# breakout.net
KiCad netlist of a schematic drawn in Altium Designer
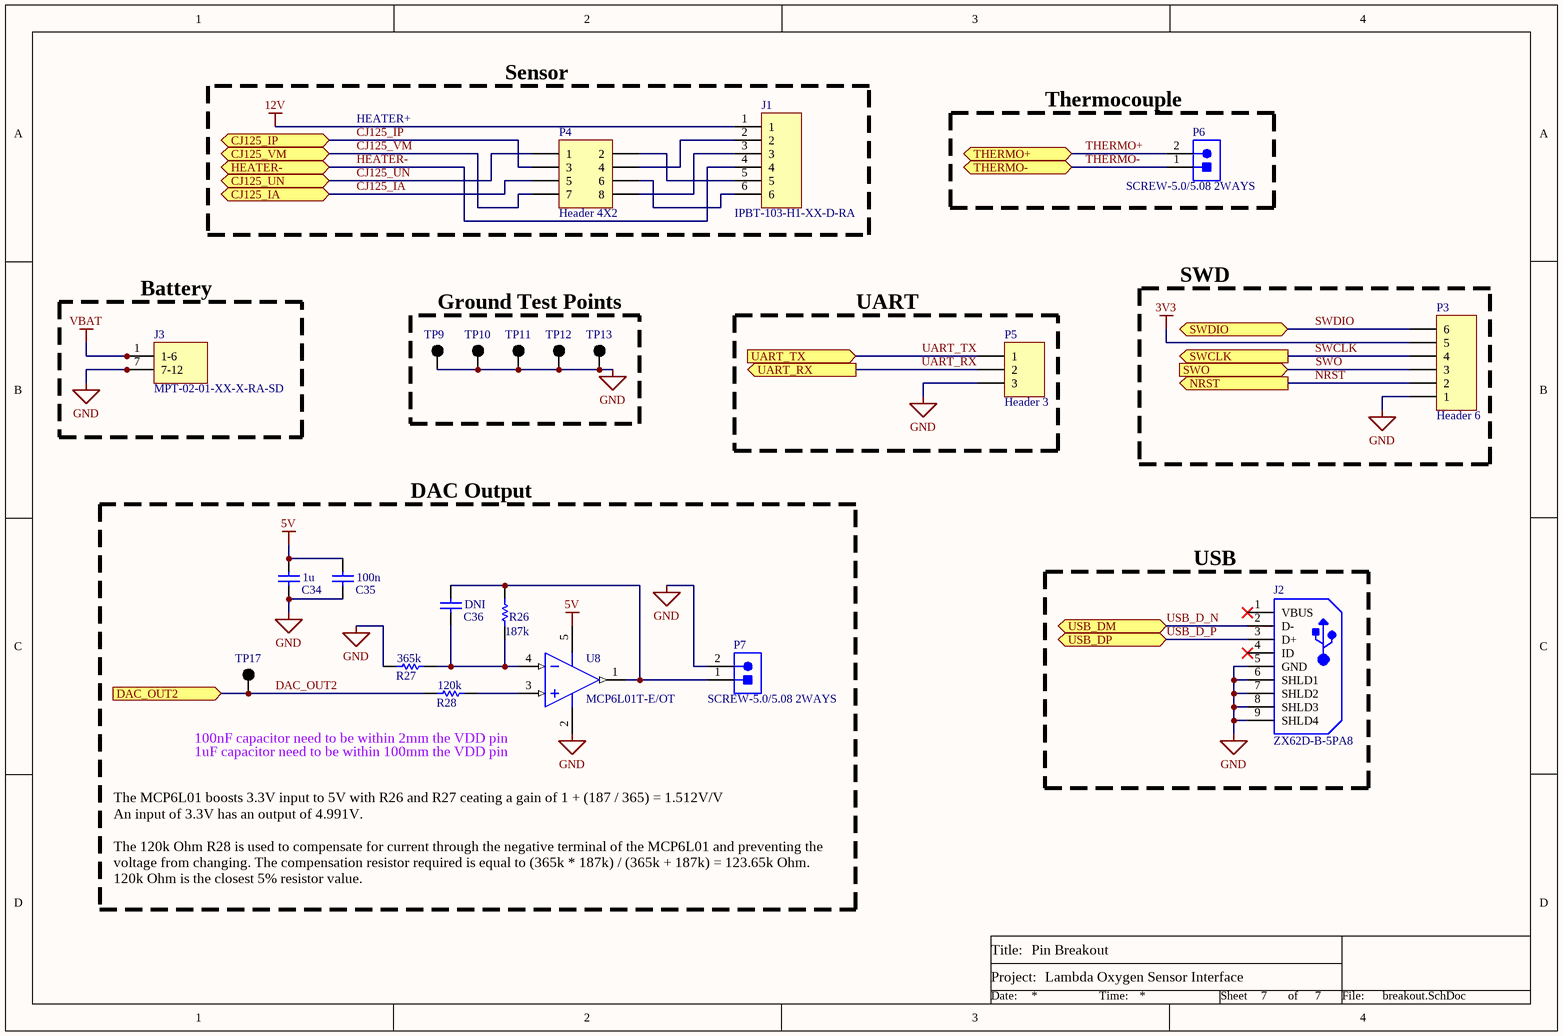
[diagram p0: breakout.SchDoc]

(export (version "E")
  (design (tool "Eeschema 10.0.6"))
  (components
    (comp (ref "C34")
      (value "1u")
      (footprint "1206")
      (description "Generic 1206 Capacitor")
      (libsource (lib "symbol_library") (part "C_1206"))
    )
    (comp (ref "C35")
      (value "100n")
      (footprint "0805")
      (description "Generic 0805 Capacitor")
      (libsource (lib "symbol_library") (part "C_0805"))
    )
    (comp (ref "C36")
      (value "DNI")
      (footprint "0805")
      (description "Generic 0805 Capacitor")
      (libsource (lib "symbol_library") (part "C_0805"))
    )
    (comp (ref "J1")
      (value "IPBT-103-H1-XX-D-RA")
      (footprint "IPBT-103-H1-XX-D-RA")
      (description "0.165 INCH DOUBLE ROW TERMINAL ASSEMBLY")
      (libsource (lib "symbol_library") (part "IPBT-103-H1-XX-D-RA"))
    )
    (comp (ref "J2")
      (value "ZX62D-B-5PA8")
      (footprint "HIRO-ZX62D-B-5PA8_V")
      (description "Micro-USB Connector Meeting USB 2.0 Standard, -30 to 85 degC, 5-Pin SMD, RoHS, Tape and Reel")
      (fields (field (name "MANUFACTURER") "HiroseElectric"))
      (libsource (lib "symbol_library") (part "Micro_USB"))
    )
    (comp (ref "J3")
      (value "MPT-02-01-XX-X-RA-SD")
      (footprint "MPT-02-01-XX-X-RA-SD")
      (libsource (lib "symbol_library") (part "MPT-02-01-XX-X-RA-SD"))
    )
    (comp (ref "P3")
      (value "Header 6")
      (footprint "HDR1X6")
      (description "Header, 6-Pin")
      (fields (field (name "PUBLISHER") "Altium Limited"))
      (libsource (lib "Miscellaneous Connectors") (part "Header 6"))
    )
    (comp (ref "P4")
      (value "Header 4X2")
      (footprint "HDR2X4")
      (description "Header, 4-Pin, Dual row")
      (fields (field (name "PUBLISHER") "Altium Limited"))
      (libsource (lib "Miscellaneous Connectors") (part "Header 4X2"))
    )
    (comp (ref "P5")
      (value "Header 3")
      (footprint "HDR1X3")
      (description "Header, 3-Pin")
      (fields (field (name "PUBLISHER") "Altium Limited"))
      (libsource (lib "Miscellaneous Connectors") (part "Header 3"))
    )
    (comp (ref "P6")
      (value "SCREW-5.0/5.08 2WAYS")
      (footprint "Degson_DG126-5.0-02P-14")
      (description "Socket, Screw Terminal Block, 2 Way, 5.0 mm Pitch, 90 Degree Angle, Through-Hole")
      (fields (field (name "MANUFACTURER") "No Vendor"))
      (libsource (lib "symbol_library") (part "Screw_Header_2"))
    )
    (comp (ref "P7")
      (value "SCREW-5.0/5.08 2WAYS")
      (footprint "Degson_DG126-5.0-02P-14")
      (description "Socket, Screw Terminal Block, 2 Way, 5.0 mm Pitch, 90 Degree Angle, Through-Hole")
      (fields (field (name "MANUFACTURER") "No Vendor"))
      (libsource (lib "symbol_library") (part "Screw_Header_2"))
    )
    (comp (ref "R26")
      (value "187k")
      (footprint "0603")
      (description "Generic 0603 Resistor")
      (libsource (lib "symbol_library") (part "R_0603"))
    )
    (comp (ref "R27")
      (value "365k")
      (footprint "0603")
      (description "Generic 0603 Resistor")
      (libsource (lib "symbol_library") (part "R_0603"))
    )
    (comp (ref "R28")
      (value "120k")
      (footprint "0603")
      (description "Generic 0603 Resistor")
      (libsource (lib "symbol_library") (part "R_0603"))
    )
    (comp (ref "TP9")
      (value "5001")
      (footprint "KSTN-5001")
      (description "Test Point, Black, 1-Pin THD, RoHS, Bulk")
      (fields (field (name "MANUFACTURER") "Keystone"))
      (libsource (lib "symbol_library") (part "TP5001"))
    )
    (comp (ref "TP10")
      (value "5001")
      (footprint "KSTN-5001")
      (description "Test Point, Black, 1-Pin THD, RoHS, Bulk")
      (fields (field (name "MANUFACTURER") "Keystone"))
      (libsource (lib "symbol_library") (part "TP5001"))
    )
    (comp (ref "TP11")
      (value "5001")
      (footprint "KSTN-5001")
      (description "Test Point, Black, 1-Pin THD, RoHS, Bulk")
      (fields (field (name "MANUFACTURER") "Keystone"))
      (libsource (lib "symbol_library") (part "TP5001"))
    )
    (comp (ref "TP12")
      (value "5001")
      (footprint "KSTN-5001")
      (description "Test Point, Black, 1-Pin THD, RoHS, Bulk")
      (fields (field (name "MANUFACTURER") "Keystone"))
      (libsource (lib "symbol_library") (part "TP5001"))
    )
    (comp (ref "TP13")
      (value "5001")
      (footprint "KSTN-5001")
      (description "Test Point, Black, 1-Pin THD, RoHS, Bulk")
      (fields (field (name "MANUFACTURER") "Keystone"))
      (libsource (lib "symbol_library") (part "TP5001"))
    )
    (comp (ref "TP17")
      (value "5001")
      (footprint "KSTN-5001")
      (description "Test Point, Black, 1-Pin THD, RoHS, Bulk")
      (fields (field (name "MANUFACTURER") "Keystone"))
      (libsource (lib "symbol_library") (part "TP5001"))
    )
    (comp (ref "U8")
      (value "MCP6L01T-E/OT")
      (footprint "DDC0005A_M")
      (description "1 MHz, 85 uA Op Amp, 5-Pin SOT-23, Extended Temperature Range")
      (libsource (lib "symbol_library") (part "MCP6L01"))
    )
  )
  (nets
    (net (code "1") (name "/CJ125_IA") (class "Default")
      (node (ref "P4") (pin "5") (pinfunction "5_5") (pintype "passive"))
    )
    (net (code "2") (name "/CJ125_IP") (class "Default")
      (node (ref "P4") (pin "3") (pinfunction "3_3") (pintype "passive"))
    )
    (net (code "3") (name "/CJ125_UN") (class "Default")
      (node (ref "P4") (pin "1") (pinfunction "1_1") (pintype "passive"))
    )
    (net (code "4") (name "/CJ125_VM") (class "Default")
      (node (ref "P4") (pin "7") (pinfunction "7_7") (pintype "passive"))
    )
    (net (code "5") (name "/DAC_OUT2") (class "Default")
      (node (ref "R28") (pin "1") (pinfunction "1_1") (pintype "passive"))
      (node (ref "TP17") (pin "1") (pintype "passive"))
    )
    (net (code "6") (name "/HEATER-") (class "Default")
      (node (ref "J1") (pin "4") (pinfunction "4_4") (pintype "passive"))
    )
    (net (code "7") (name "/NRST") (class "Default")
      (node (ref "P3") (pin "2") (pinfunction "2_2") (pintype "passive"))
    )
    (net (code "8") (name "/SWCLK") (class "Default")
      (node (ref "P3") (pin "4") (pinfunction "4_4") (pintype "passive"))
    )
    (net (code "9") (name "/SWDIO") (class "Default")
      (node (ref "P3") (pin "6") (pinfunction "6_6") (pintype "passive"))
    )
    (net (code "10") (name "/SWO") (class "Default")
      (node (ref "P3") (pin "3") (pinfunction "3_3") (pintype "passive"))
    )
    (net (code "11") (name "/THERMO+") (class "Default")
      (node (ref "P6") (pin "2") (pinfunction "2_2") (pintype "passive"))
    )
    (net (code "12") (name "/THERMO-") (class "Default")
      (node (ref "P6") (pin "1") (pinfunction "1_1") (pintype "passive"))
    )
    (net (code "13") (name "/UART_RX") (class "Default")
      (node (ref "P5") (pin "2") (pinfunction "2_2") (pintype "passive"))
    )
    (net (code "14") (name "/UART_TX") (class "Default")
      (node (ref "P5") (pin "1") (pinfunction "1_1") (pintype "passive"))
    )
    (net (code "15") (name "/USB_D_N") (class "Default")
      (node (ref "J2") (pin "2") (pinfunction "D-_2") (pintype "passive"))
    )
    (net (code "16") (name "/USB_D_P") (class "Default")
      (node (ref "J2") (pin "3") (pinfunction "D+_3") (pintype "passive"))
    )
    (net (code "17") (name "3V3") (class "Default")
      (node (ref "P3") (pin "5") (pinfunction "5_5") (pintype "passive"))
    )
    (net (code "18") (name "5V") (class "Default")
      (node (ref "C34") (pin "2") (pinfunction "2_2") (pintype "passive"))
      (node (ref "C35") (pin "2") (pinfunction "2_2") (pintype "passive"))
      (node (ref "U8") (pin "5") (pinfunction "VDD_5") (pintype "power_in"))
    )
    (net (code "19") (name "12V") (class "Default")
      (node (ref "J1") (pin "1") (pinfunction "1_1") (pintype "passive"))
    )
    (net (code "20") (name "GND") (class "Default")
      (node (ref "C34") (pin "1") (pinfunction "1_1") (pintype "passive"))
      (node (ref "C35") (pin "1") (pinfunction "1_1") (pintype "passive"))
      (node (ref "J2") (pin "5") (pinfunction "GND_5") (pintype "passive"))
      (node (ref "J2") (pin "6") (pinfunction "SHLD1_6") (pintype "passive"))
      (node (ref "J2") (pin "7") (pinfunction "SHLD2_7") (pintype "passive"))
      (node (ref "J2") (pin "8") (pinfunction "SHLD3_8") (pintype "passive"))
      (node (ref "J2") (pin "9") (pinfunction "SHLD4_9") (pintype "passive"))
      (node (ref "J3") (pin "10") (pinfunction "10_10") (pintype "passive"))
      (node (ref "J3") (pin "11") (pinfunction "11_11") (pintype "passive"))
      (node (ref "J3") (pin "12") (pinfunction "12_12") (pintype "passive"))
      (node (ref "J3") (pin "7") (pinfunction "7-12_7") (pintype "passive"))
      (node (ref "J3") (pin "8") (pinfunction "8_8") (pintype "passive"))
      (node (ref "J3") (pin "9") (pinfunction "9_9") (pintype "passive"))
      (node (ref "P3") (pin "1") (pinfunction "1_1") (pintype "passive"))
      (node (ref "P5") (pin "3") (pinfunction "3_3") (pintype "passive"))
      (node (ref "P7") (pin "2") (pinfunction "2_2") (pintype "passive"))
      (node (ref "R27") (pin "1") (pinfunction "1_1") (pintype "passive"))
      (node (ref "TP10") (pin "1") (pintype "passive"))
      (node (ref "TP11") (pin "1") (pintype "passive"))
      (node (ref "TP12") (pin "1") (pintype "passive"))
      (node (ref "TP13") (pin "1") (pintype "passive"))
      (node (ref "TP9") (pin "1") (pintype "passive"))
      (node (ref "U8") (pin "2") (pinfunction "VSS_2") (pintype "power_in"))
    )
    (net (code "21") (name "Net-(J1-Pad2)") (class "Default")
      (node (ref "J1") (pin "2") (pinfunction "2_2") (pintype "passive"))
      (node (ref "P4") (pin "4") (pinfunction "4_4") (pintype "passive"))
    )
    (net (code "22") (name "Net-(J1-Pad3)") (class "Default")
      (node (ref "J1") (pin "3") (pinfunction "3_3") (pintype "passive"))
      (node (ref "P4") (pin "8") (pinfunction "8_8") (pintype "passive"))
    )
    (net (code "23") (name "Net-(J1-Pad5)") (class "Default")
      (node (ref "J1") (pin "5") (pinfunction "5_5") (pintype "passive"))
      (node (ref "P4") (pin "2") (pinfunction "2_2") (pintype "passive"))
    )
    (net (code "24") (name "Net-(J1-Pad6)") (class "Default")
      (node (ref "J1") (pin "6") (pinfunction "6_6") (pintype "passive"))
      (node (ref "P4") (pin "6") (pinfunction "6_6") (pintype "passive"))
    )
    (net (code "25") (name "Net-(U8-VIN+)") (class "Default")
      (node (ref "R28") (pin "2") (pinfunction "2_2") (pintype "passive"))
      (node (ref "U8") (pin "3") (pinfunction "VIN+_3") (pintype "input"))
    )
    (net (code "26") (name "Net-(U8-VIN-)") (class "Default")
      (node (ref "C36") (pin "1") (pinfunction "1_1") (pintype "passive"))
      (node (ref "R26") (pin "1") (pinfunction "1_1") (pintype "passive"))
      (node (ref "R27") (pin "2") (pinfunction "2_2") (pintype "passive"))
      (node (ref "U8") (pin "4") (pinfunction "VIN-_4") (pintype "input"))
    )
    (net (code "27") (name "Net-(U8-VOUT)") (class "Default")
      (node (ref "C36") (pin "2") (pinfunction "2_2") (pintype "passive"))
      (node (ref "P7") (pin "1") (pinfunction "1_1") (pintype "passive"))
      (node (ref "R26") (pin "2") (pinfunction "2_2") (pintype "passive"))
      (node (ref "U8") (pin "1") (pinfunction "VOUT_1") (pintype "output"))
    )
    (net (code "28") (name "VBAT") (class "Default")
      (node (ref "J3") (pin "1") (pinfunction "1-6_1") (pintype "passive"))
      (node (ref "J3") (pin "2") (pinfunction "2_2") (pintype "passive"))
      (node (ref "J3") (pin "3") (pinfunction "3_3") (pintype "passive"))
      (node (ref "J3") (pin "4") (pinfunction "4_4") (pintype "passive"))
      (node (ref "J3") (pin "5") (pinfunction "5_5") (pintype "passive"))
      (node (ref "J3") (pin "6") (pinfunction "6_6") (pintype "passive"))
    )
    (net (code "29") (name "unconnected-(J2-ID-Pad4)") (class "Default")
      (node (ref "J2") (pin "4") (pinfunction "ID_4") (pintype "passive+no_connect"))
    )
    (net (code "30") (name "unconnected-(J2-VBUS-Pad1)") (class "Default")
      (node (ref "J2") (pin "1") (pinfunction "VBUS_1") (pintype "passive+no_connect"))
    )
  )
)
